# XIAO_RP2040_v1_22.net
KiCad netlist of a schematic drawn in EAGLE
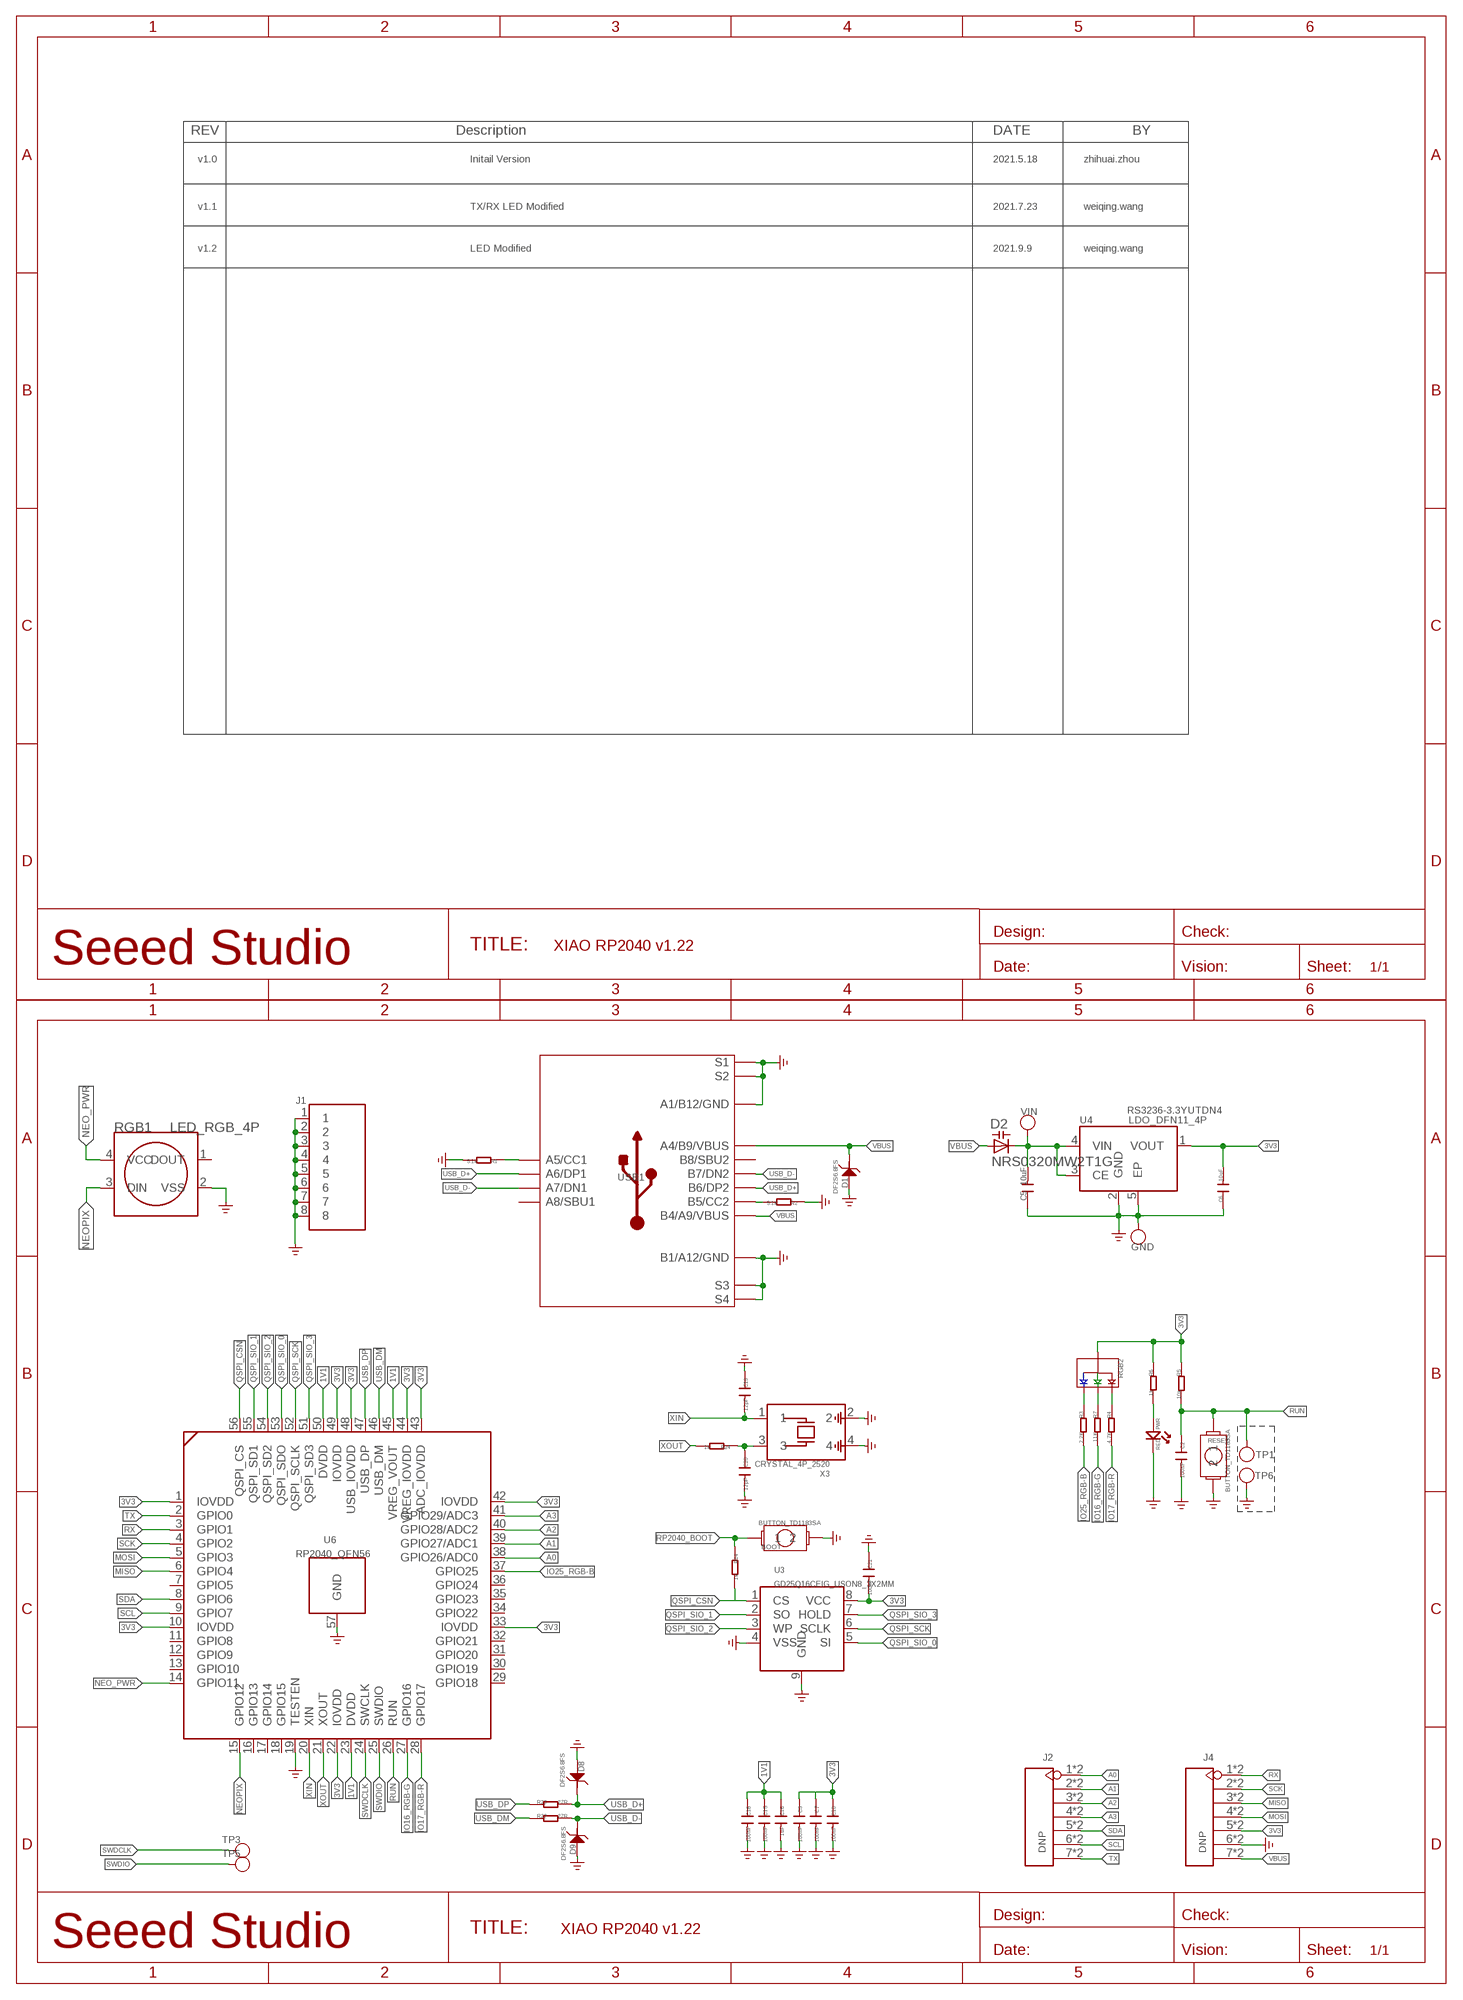
[diagram p0: schematic, sheet 1]

(export (version "E")
  (design (tool "Eeschema 10.0.6"))
  (components
    (comp (ref "BOOT")
      (value "BUTTON_TD1183SA")
      (footprint "eagle-import:BUTTON_TD1183SA")
      (libsource (lib "eagle-import") (part "BUTTON_TD1183SA"))
    )
    (comp (ref "C2")
      (value "100nF")
      (footprint "eagle-import:0201_NORMAL_NOSILK")
      (libsource (lib "eagle-import") (part "CAP{backslash}0201NNS"))
    )
    (comp (ref "C3")
      (value "100nF")
      (footprint "eagle-import:0201_NORMAL_NOSILK")
      (libsource (lib "eagle-import") (part "CAP{backslash}0201NNS"))
    )
    (comp (ref "C5")
      (value "10uF")
      (footprint "eagle-import:C0402")
      (libsource (lib "eagle-import") (part "C-0402"))
    )
    (comp (ref "C6")
      (value "10uF")
      (footprint "eagle-import:C0402")
      (libsource (lib "eagle-import") (part "C-0402"))
    )
    (comp (ref "C7")
      (value "100nF")
      (footprint "eagle-import:0201_NORMAL_NOSILK")
      (libsource (lib "eagle-import") (part "CAP{backslash}0201NNS"))
    )
    (comp (ref "C10")
      (value "100nF")
      (footprint "eagle-import:0201_NORMAL_NOSILK")
      (libsource (lib "eagle-import") (part "CAP{backslash}0201NNS"))
    )
    (comp (ref "C15")
      (value "100nF")
      (footprint "eagle-import:0201_NORMAL_NOSILK")
      (libsource (lib "eagle-import") (part "CAP{backslash}0201NNS"))
    )
    (comp (ref "C16")
      (value "1uF")
      (footprint "eagle-import:0201_NORMAL_NOSILK")
      (libsource (lib "eagle-import") (part "CAP{backslash}0201NNS"))
    )
    (comp (ref "C18")
      (value "100nF")
      (footprint "eagle-import:0201_NORMAL_NOSILK")
      (libsource (lib "eagle-import") (part "CAP{backslash}0201NNS"))
    )
    (comp (ref "C19")
      (value "12pF")
      (footprint "eagle-import:0201_NORMAL_NOSILK")
      (libsource (lib "eagle-import") (part "CAP{backslash}0201NNS"))
    )
    (comp (ref "C20")
      (value "12pF")
      (footprint "eagle-import:0201_NORMAL_NOSILK")
      (libsource (lib "eagle-import") (part "CAP{backslash}0201NNS"))
    )
    (comp (ref "C21")
      (value "100nF")
      (footprint "eagle-import:0201_NORMAL_NOSILK")
      (libsource (lib "eagle-import") (part "CAP{backslash}0201NNS"))
    )
    (comp (ref "D1")
      (value "DF2S6.8FS")
      (footprint "eagle-import:SOD-923")
      (libsource (lib "eagle-import") (part "D-ESD-2P'DF2S6.8FS'"))
    )
    (comp (ref "D2")
      (value "NRS0320MW2T1G")
      (footprint "eagle-import:SOD523")
      (libsource (lib "eagle-import") (part "DIODE_CAPACITANCE-SOD523"))
    )
    (comp (ref "D8")
      (value "DF2S6.8FS")
      (footprint "eagle-import:SOD-923")
      (libsource (lib "eagle-import") (part "D-ESD-2P'DF2S6.8FS'"))
    )
    (comp (ref "D9")
      (value "DF2S6.8FS")
      (footprint "eagle-import:SOD-923")
      (libsource (lib "eagle-import") (part "D-ESD-2P'DF2S6.8FS'"))
    )
    (comp (ref "GND")
      (value "TEST-POINT'4080'")
      (footprint "eagle-import:TP-80X40MIL")
      (libsource (lib "eagle-import") (part "TEST-POINT'4080'"))
    )
    (comp (ref "J1")
      (value "SHIELDING-COVER-XIAO_RP2040_PRD")
      (footprint "eagle-import:SHIELDING-COVER_XIAO_RP2040_PRD")
      (libsource (lib "eagle-import") (part "SHIELDING-COVER-XIAO_RP2040_PRD"))
    )
    (comp (ref "J2")
      (value "DNP")
      (footprint "eagle-import:H7-HALF-HOLE-2.54")
      (libsource (lib "eagle-import") (part "HEADER-7P-HALF-HOLE-2.54"))
    )
    (comp (ref "J4")
      (value "DNP")
      (footprint "eagle-import:H7-HALF-HOLE-2.54")
      (libsource (lib "eagle-import") (part "HEADER-7P-HALF-HOLE-2.54"))
    )
    (comp (ref "PWR")
      (value "RED")
      (footprint "eagle-import:LED-0402")
      (libsource (lib "eagle-import") (part "LED-0402"))
    )
    (comp (ref "R1")
      (value "5.1k")
      (footprint "eagle-import:R0201")
      (libsource (lib "eagle-import") (part "R-0201"))
    )
    (comp (ref "R2")
      (value "5.1k")
      (footprint "eagle-import:R0201")
      (libsource (lib "eagle-import") (part "R-0201"))
    )
    (comp (ref "R3")
      (value "2.2K")
      (footprint "eagle-import:R0201")
      (libsource (lib "eagle-import") (part "R-0201"))
    )
    (comp (ref "R4")
      (value "4.7K")
      (footprint "eagle-import:R0201")
      (libsource (lib "eagle-import") (part "R-0201"))
    )
    (comp (ref "R5")
      (value "10k")
      (footprint "eagle-import:R0201")
      (libsource (lib "eagle-import") (part "R-0201"))
    )
    (comp (ref "R6")
      (value "1k")
      (footprint "eagle-import:R0201")
      (libsource (lib "eagle-import") (part "R-0201"))
    )
    (comp (ref "R7")
      (value "11K")
      (footprint "eagle-import:R0201")
      (libsource (lib "eagle-import") (part "R-0201"))
    )
    (comp (ref "R14")
      (value "1k")
      (footprint "eagle-import:R0201")
      (libsource (lib "eagle-import") (part "R-0201"))
    )
    (comp (ref "R22")
      (value "27R")
      (footprint "eagle-import:R0201")
      (libsource (lib "eagle-import") (part "R-0201"))
    )
    (comp (ref "R23")
      (value "27R")
      (footprint "eagle-import:R0201")
      (libsource (lib "eagle-import") (part "R-0201"))
    )
    (comp (ref "R24")
      (value "1k")
      (footprint "eagle-import:R0201")
      (libsource (lib "eagle-import") (part "R-0201"))
    )
    (comp (ref "RESET")
      (value "BUTTON_TD1183SA")
      (footprint "eagle-import:BUTTON_TD1183SA")
      (libsource (lib "eagle-import") (part "BUTTON_TD1183SA"))
    )
    (comp (ref "RGB1")
      (value "LED_RGB_4P")
      (footprint "eagle-import:LED_RGB_2427")
      (libsource (lib "eagle-import") (part "LED_RGB_4P"))
    )
    (comp (ref "RGB2")
      (value "LED_RGB_4P-1010")
      (footprint "eagle-import:1010-4P")
      (libsource (lib "eagle-import") (part "LED_RGB_4P-1010"))
    )
    (comp (ref "TP1")
      (value "TEST-POINT'4545'")
      (footprint "eagle-import:TP-D45MIL")
      (fields (field (name "PARTNO") "DNP"))
      (libsource (lib "eagle-import") (part "TEST-POINT'4545'"))
    )
    (comp (ref "TP3")
      (value "TEST-POINT'4545'")
      (footprint "eagle-import:TP-D45MIL")
      (fields (field (name "PARTNO") "DNP"))
      (libsource (lib "eagle-import") (part "TEST-POINT'4545'"))
    )
    (comp (ref "TP5")
      (value "TEST-POINT'4545'")
      (footprint "eagle-import:TP-D45MIL")
      (fields (field (name "PARTNO") "DNP"))
      (libsource (lib "eagle-import") (part "TEST-POINT'4545'"))
    )
    (comp (ref "TP6")
      (value "TEST-POINT'4545'")
      (footprint "eagle-import:TP-D45MIL")
      (fields (field (name "PARTNO") "DNP"))
      (libsource (lib "eagle-import") (part "TEST-POINT'4545'"))
    )
    (comp (ref "U3")
      (value "GD25Q16CEIG_USON8_3X2MM")
      (footprint "eagle-import:GD25Q16CEIG_USON8_3X2MM")
      (libsource (lib "eagle-import") (part "GD25Q16CEIG_USON8_3X2MM"))
    )
    (comp (ref "U4")
      (value "LDO_DFN11_4P")
      (footprint "eagle-import:LDO_DFN1_1_4P")
      (libsource (lib "eagle-import") (part "LDO_DFN11_4P"))
    )
    (comp (ref "U6")
      (value "RP2040_QFN56")
      (footprint "eagle-import:RP2040_QFN56")
      (libsource (lib "eagle-import") (part "RP2040_QFN56"))
    )
    (comp (ref "USB1")
      (value "USB2.0-TYPE-C")
      (footprint "eagle-import:USB2.0-TYPE-C")
      (libsource (lib "eagle-import") (part "USB2.0-TYPE-C"))
    )
    (comp (ref "VIN")
      (value "TEST-POINT'4080'")
      (footprint "eagle-import:TP-80X40MIL")
      (libsource (lib "eagle-import") (part "TEST-POINT'4080'"))
    )
    (comp (ref "X3")
      (value "CRYSTAL_4P_2520")
      (footprint "eagle-import:CRYSTAL_4P_2520")
      (libsource (lib "eagle-import") (part "CRYSTAL_4P_2520"))
    )
  )
  (nets
    (net (code "1") (name "1V1") (class "Default")
      (node (ref "C15") (pin "1") (pinfunction "1_1") (pintype "passive"))
      (node (ref "C16") (pin "1") (pinfunction "1_1") (pintype "passive"))
      (node (ref "C18") (pin "1") (pinfunction "1_1") (pintype "passive"))
      (node (ref "U6") (pin "23") (pinfunction "DVDD_23") (pintype "bidirectional"))
      (node (ref "U6") (pin "45") (pinfunction "VREG_VOUT_45") (pintype "bidirectional"))
      (node (ref "U6") (pin "50") (pinfunction "DVDD_50") (pintype "bidirectional"))
    )
    (net (code "2") (name "3V3") (class "Default")
      (node (ref "C10") (pin "1") (pinfunction "1_1") (pintype "passive"))
      (node (ref "C21") (pin "2") (pinfunction "2_2") (pintype "passive"))
      (node (ref "C3") (pin "1") (pinfunction "1_1") (pintype "passive"))
      (node (ref "C6") (pin "2") (pinfunction "2_2") (pintype "passive"))
      (node (ref "C7") (pin "1") (pinfunction "1_1") (pintype "passive"))
      (node (ref "J4") (pin "17") (pinfunction "5_17") (pintype "bidirectional"))
      (node (ref "J4") (pin "5") (pinfunction "5_5") (pintype "bidirectional"))
      (node (ref "R5") (pin "1") (pinfunction "1_1") (pintype "passive"))
      (node (ref "R6") (pin "1") (pinfunction "1_1") (pintype "passive"))
      (node (ref "RGB2") (pin "+") (pinfunction "+_+") (pintype "bidirectional"))
      (node (ref "U3") (pin "8") (pinfunction "VCC_8") (pintype "bidirectional"))
      (node (ref "U4") (pin "1") (pinfunction "VOUT_1") (pintype "bidirectional"))
      (node (ref "U6") (pin "1") (pinfunction "IOVDD_1") (pintype "bidirectional"))
      (node (ref "U6") (pin "10") (pinfunction "IOVDD_10") (pintype "bidirectional"))
      (node (ref "U6") (pin "22") (pinfunction "IOVDD_22") (pintype "bidirectional"))
      (node (ref "U6") (pin "33") (pinfunction "IOVDD_33") (pintype "bidirectional"))
      (node (ref "U6") (pin "42") (pinfunction "IOVDD_42") (pintype "bidirectional"))
      (node (ref "U6") (pin "43") (pinfunction "ADC_IOVDD_43") (pintype "bidirectional"))
      (node (ref "U6") (pin "44") (pinfunction "VREG_IOVDD_44") (pintype "bidirectional"))
      (node (ref "U6") (pin "48") (pinfunction "USB_IOVDD_48") (pintype "bidirectional"))
      (node (ref "U6") (pin "49") (pinfunction "IOVDD_49") (pintype "bidirectional"))
    )
    (net (code "3") (name "A0") (class "Default")
      (node (ref "J2") (pin "1") (pinfunction "1_1") (pintype "bidirectional"))
      (node (ref "J2") (pin "13") (pinfunction "1_13") (pintype "bidirectional"))
      (node (ref "U6") (pin "38") (pinfunction "GPIO26/ADC0_38") (pintype "bidirectional"))
    )
    (net (code "4") (name "A1") (class "Default")
      (node (ref "J2") (pin "14") (pinfunction "2_14") (pintype "bidirectional"))
      (node (ref "J2") (pin "2") (pinfunction "2_2") (pintype "bidirectional"))
      (node (ref "U6") (pin "39") (pinfunction "GPIO27/ADC1_39") (pintype "bidirectional"))
    )
    (net (code "5") (name "A2") (class "Default")
      (node (ref "J2") (pin "15") (pinfunction "3_15") (pintype "bidirectional"))
      (node (ref "J2") (pin "3") (pinfunction "3_3") (pintype "bidirectional"))
      (node (ref "U6") (pin "40") (pinfunction "GPIO28/ADC2_40") (pintype "bidirectional"))
    )
    (net (code "6") (name "A3") (class "Default")
      (node (ref "J2") (pin "16") (pinfunction "4_16") (pintype "bidirectional"))
      (node (ref "J2") (pin "4") (pinfunction "4_4") (pintype "bidirectional"))
      (node (ref "U6") (pin "41") (pinfunction "GPIO29/ADC3_41") (pintype "bidirectional"))
    )
    (net (code "7") (name "GND_POWER") (class "Default")
      (node (ref "BOOT") (pin "2") (pinfunction "2_2") (pintype "bidirectional"))
      (node (ref "C10") (pin "2") (pinfunction "2_2") (pintype "passive"))
      (node (ref "C15") (pin "2") (pinfunction "2_2") (pintype "passive"))
      (node (ref "C16") (pin "2") (pinfunction "2_2") (pintype "passive"))
      (node (ref "C18") (pin "2") (pinfunction "2_2") (pintype "passive"))
      (node (ref "C19") (pin "1") (pinfunction "1_1") (pintype "passive"))
      (node (ref "C2") (pin "2") (pinfunction "2_2") (pintype "passive"))
      (node (ref "C20") (pin "2") (pinfunction "2_2") (pintype "passive"))
      (node (ref "C21") (pin "1") (pinfunction "1_1") (pintype "passive"))
      (node (ref "C3") (pin "2") (pinfunction "2_2") (pintype "passive"))
      (node (ref "C5") (pin "1") (pinfunction "1_1") (pintype "passive"))
      (node (ref "C6") (pin "1") (pinfunction "1_1") (pintype "passive"))
      (node (ref "C7") (pin "2") (pinfunction "2_2") (pintype "passive"))
      (node (ref "D1") (pin "2") (pinfunction "1_2") (pintype "bidirectional"))
      (node (ref "D8") (pin "2") (pinfunction "1_2") (pintype "bidirectional"))
      (node (ref "D9") (pin "2") (pinfunction "1_2") (pintype "bidirectional"))
      (node (ref "GND") (pin "1") (pinfunction "T_1") (pintype "bidirectional"))
      (node (ref "J1") (pin "1") (pinfunction "1_1") (pintype "bidirectional"))
      (node (ref "J1") (pin "2") (pinfunction "2_2") (pintype "bidirectional"))
      (node (ref "J1") (pin "3") (pinfunction "3_3") (pintype "bidirectional"))
      (node (ref "J1") (pin "4") (pinfunction "4_4") (pintype "bidirectional"))
      (node (ref "J1") (pin "5") (pinfunction "5_5") (pintype "bidirectional"))
      (node (ref "J1") (pin "6") (pinfunction "6_6") (pintype "bidirectional"))
      (node (ref "J1") (pin "7") (pinfunction "7_7") (pintype "bidirectional"))
      (node (ref "J1") (pin "8") (pinfunction "8_8") (pintype "bidirectional"))
      (node (ref "J4") (pin "18") (pinfunction "6_18") (pintype "bidirectional"))
      (node (ref "J4") (pin "6") (pinfunction "6_6") (pintype "bidirectional"))
      (node (ref "PWR") (pin "-") (pinfunction "-_-") (pintype "passive"))
      (node (ref "R1") (pin "2") (pinfunction "2_2") (pintype "passive"))
      (node (ref "R2") (pin "1") (pinfunction "1_1") (pintype "passive"))
      (node (ref "RESET") (pin "2") (pinfunction "2_2") (pintype "bidirectional"))
      (node (ref "RGB1") (pin "2") (pinfunction "VSS_2") (pintype "bidirectional"))
      (node (ref "TP6") (pin "T") (pinfunction "T_T") (pintype "bidirectional"))
      (node (ref "U3") (pin "4") (pinfunction "VSS_4") (pintype "bidirectional"))
      (node (ref "U3") (pin "9") (pinfunction "GND_9") (pintype "bidirectional"))
      (node (ref "U4") (pin "2") (pinfunction "GND_2") (pintype "bidirectional"))
      (node (ref "U4") (pin "5") (pinfunction "EP_5") (pintype "bidirectional"))
      (node (ref "U6") (pin "19") (pinfunction "TESTEN_19") (pintype "bidirectional"))
      (node (ref "U6") (pin "57") (pinfunction "GND_57") (pintype "bidirectional"))
      (node (ref "USB1") (pin "A1_B12") (pinfunction "A1/B12/GND_A1_B12") (pintype "bidirectional"))
      (node (ref "USB1") (pin "B1_A12") (pinfunction "B1/A12/GND_B1_A12") (pintype "bidirectional"))
      (node (ref "USB1") (pin "S1") (pinfunction "S1_S1") (pintype "bidirectional"))
      (node (ref "USB1") (pin "S2") (pinfunction "S2_S2") (pintype "bidirectional"))
      (node (ref "USB1") (pin "S3") (pinfunction "S3_S3") (pintype "bidirectional"))
      (node (ref "USB1") (pin "S4") (pinfunction "S4_S4") (pintype "bidirectional"))
      (node (ref "USB1") (pin "S5") (pinfunction "S1_S5") (pintype "bidirectional"))
      (node (ref "USB1") (pin "S6") (pinfunction "S2_S6") (pintype "bidirectional"))
      (node (ref "X3") (pin "2") (pinfunction "2_2") (pintype "bidirectional"))
      (node (ref "X3") (pin "4") (pinfunction "4_4") (pintype "bidirectional"))
    )
    (net (code "8") (name "IO16_RGB-G") (class "Default")
      (node (ref "R7") (pin "2") (pinfunction "2_2") (pintype "passive"))
      (node (ref "U6") (pin "27") (pinfunction "GPIO16_27") (pintype "bidirectional"))
    )
    (net (code "9") (name "IO17_RGB-R") (class "Default")
      (node (ref "R4") (pin "2") (pinfunction "2_2") (pintype "passive"))
      (node (ref "U6") (pin "28") (pinfunction "GPIO17_28") (pintype "bidirectional"))
    )
    (net (code "10") (name "IO25_RGB-B") (class "Default")
      (node (ref "R3") (pin "2") (pinfunction "2_2") (pintype "passive"))
      (node (ref "U6") (pin "37") (pinfunction "GPIO25_37") (pintype "bidirectional"))
    )
    (net (code "11") (name "MISO") (class "Default")
      (node (ref "J4") (pin "15") (pinfunction "3_15") (pintype "bidirectional"))
      (node (ref "J4") (pin "3") (pinfunction "3_3") (pintype "bidirectional"))
      (node (ref "U6") (pin "6") (pinfunction "GPIO4_6") (pintype "bidirectional"))
    )
    (net (code "12") (name "MOSI") (class "Default")
      (node (ref "J4") (pin "16") (pinfunction "4_16") (pintype "bidirectional"))
      (node (ref "J4") (pin "4") (pinfunction "4_4") (pintype "bidirectional"))
      (node (ref "U6") (pin "5") (pinfunction "GPIO3_5") (pintype "bidirectional"))
    )
    (net (code "13") (name "NEOPIX") (class "Default")
      (node (ref "RGB1") (pin "3") (pinfunction "DIN_3") (pintype "bidirectional"))
      (node (ref "U6") (pin "15") (pinfunction "GPIO12_15") (pintype "bidirectional"))
    )
    (net (code "14") (name "NEO_PWR") (class "Default")
      (node (ref "RGB1") (pin "4") (pinfunction "VCC_4") (pintype "bidirectional"))
      (node (ref "U6") (pin "14") (pinfunction "GPIO11_14") (pintype "bidirectional"))
    )
    (net (code "15") (name "Net-(C20-Pad1)") (class "Default")
      (node (ref "C20") (pin "1") (pinfunction "1_1") (pintype "passive"))
      (node (ref "R24") (pin "1") (pinfunction "1_1") (pintype "passive"))
      (node (ref "X3") (pin "3") (pinfunction "3_3") (pintype "bidirectional"))
    )
    (net (code "16") (name "Net-(PWR-Pad+)") (class "Default")
      (node (ref "PWR") (pin "+") (pinfunction "+_+") (pintype "passive"))
      (node (ref "R6") (pin "2") (pinfunction "2_2") (pintype "passive"))
    )
    (net (code "17") (name "Net-(R3-Pad1)") (class "Default")
      (node (ref "R3") (pin "1") (pinfunction "1_1") (pintype "passive"))
      (node (ref "RGB2") (pin "B-") (pinfunction "B-_B-") (pintype "bidirectional"))
    )
    (net (code "18") (name "Net-(R4-Pad1)") (class "Default")
      (node (ref "R4") (pin "1") (pinfunction "1_1") (pintype "passive"))
      (node (ref "RGB2") (pin "R-") (pinfunction "R-_R-") (pintype "bidirectional"))
    )
    (net (code "19") (name "Net-(R7-Pad1)") (class "Default")
      (node (ref "R7") (pin "1") (pinfunction "1_1") (pintype "passive"))
      (node (ref "RGB2") (pin "G-") (pinfunction "G-_G-") (pintype "bidirectional"))
    )
    (net (code "20") (name "Net-(U4-CE)") (class "Default")
      (node (ref "C5") (pin "2") (pinfunction "2_2") (pintype "passive"))
      (node (ref "D2") (pin "C") (pinfunction "C_C") (pintype "passive"))
      (node (ref "U4") (pin "3") (pinfunction "CE_3") (pintype "bidirectional"))
      (node (ref "U4") (pin "4") (pinfunction "VIN_4") (pintype "bidirectional"))
      (node (ref "VIN") (pin "1") (pinfunction "T_1") (pintype "bidirectional"))
    )
    (net (code "21") (name "Net-(USB1-A5{slash}CC1)") (class "Default")
      (node (ref "R1") (pin "1") (pinfunction "1_1") (pintype "passive"))
      (node (ref "USB1") (pin "A5") (pinfunction "A5/CC1_A5") (pintype "bidirectional"))
    )
    (net (code "22") (name "Net-(USB1-B5{slash}CC2)") (class "Default")
      (node (ref "R2") (pin "2") (pinfunction "2_2") (pintype "passive"))
      (node (ref "USB1") (pin "B5") (pinfunction "B5/CC2_B5") (pintype "bidirectional"))
    )
    (net (code "23") (name "QSPI_CSN") (class "Default")
      (node (ref "R14") (pin "2") (pinfunction "2_2") (pintype "passive"))
      (node (ref "U3") (pin "1") (pinfunction "CS_1") (pintype "bidirectional"))
      (node (ref "U6") (pin "56") (pinfunction "QSPI_CS_56") (pintype "bidirectional"))
    )
    (net (code "24") (name "QSPI_SCK") (class "Default")
      (node (ref "U3") (pin "6") (pinfunction "SCLK_6") (pintype "bidirectional"))
      (node (ref "U6") (pin "52") (pinfunction "QSPI_SCLK_52") (pintype "bidirectional"))
    )
    (net (code "25") (name "QSPI_SIO_0") (class "Default")
      (node (ref "U3") (pin "5") (pinfunction "SI_5") (pintype "bidirectional"))
      (node (ref "U6") (pin "53") (pinfunction "QSPI_SDO_53") (pintype "bidirectional"))
    )
    (net (code "26") (name "QSPI_SIO_1") (class "Default")
      (node (ref "U3") (pin "2") (pinfunction "SO_2") (pintype "bidirectional"))
      (node (ref "U6") (pin "55") (pinfunction "QSPI_SD1_55") (pintype "bidirectional"))
    )
    (net (code "27") (name "QSPI_SIO_2") (class "Default")
      (node (ref "U3") (pin "3") (pinfunction "WP_3") (pintype "bidirectional"))
      (node (ref "U6") (pin "54") (pinfunction "QSPI_SD2_54") (pintype "bidirectional"))
    )
    (net (code "28") (name "QSPI_SIO_3") (class "Default")
      (node (ref "U3") (pin "7") (pinfunction "HOLD_7") (pintype "bidirectional"))
      (node (ref "U6") (pin "51") (pinfunction "QSPI_SD3_51") (pintype "bidirectional"))
    )
    (net (code "29") (name "RP2040_BOOT") (class "Default")
      (node (ref "BOOT") (pin "1") (pinfunction "1_1") (pintype "bidirectional"))
      (node (ref "R14") (pin "1") (pinfunction "1_1") (pintype "passive"))
    )
    (net (code "30") (name "RUN") (class "Default")
      (node (ref "C2") (pin "1") (pinfunction "1_1") (pintype "passive"))
      (node (ref "R5") (pin "2") (pinfunction "2_2") (pintype "passive"))
      (node (ref "RESET") (pin "1") (pinfunction "1_1") (pintype "bidirectional"))
      (node (ref "TP1") (pin "T") (pinfunction "T_T") (pintype "bidirectional"))
      (node (ref "U6") (pin "26") (pinfunction "RUN_26") (pintype "bidirectional"))
    )
    (net (code "31") (name "RX") (class "Default")
      (node (ref "J4") (pin "1") (pinfunction "1_1") (pintype "bidirectional"))
      (node (ref "J4") (pin "13") (pinfunction "1_13") (pintype "bidirectional"))
      (node (ref "U6") (pin "3") (pinfunction "GPIO1_3") (pintype "bidirectional"))
    )
    (net (code "32") (name "SCK") (class "Default")
      (node (ref "J4") (pin "14") (pinfunction "2_14") (pintype "bidirectional"))
      (node (ref "J4") (pin "2") (pinfunction "2_2") (pintype "bidirectional"))
      (node (ref "U6") (pin "4") (pinfunction "GPIO2_4") (pintype "bidirectional"))
    )
    (net (code "33") (name "SCL") (class "Default")
      (node (ref "J2") (pin "18") (pinfunction "6_18") (pintype "bidirectional"))
      (node (ref "J2") (pin "6") (pinfunction "6_6") (pintype "bidirectional"))
      (node (ref "U6") (pin "9") (pinfunction "GPIO7_9") (pintype "bidirectional"))
    )
    (net (code "34") (name "SDA") (class "Default")
      (node (ref "J2") (pin "17") (pinfunction "5_17") (pintype "bidirectional"))
      (node (ref "J2") (pin "5") (pinfunction "5_5") (pintype "bidirectional"))
      (node (ref "U6") (pin "8") (pinfunction "GPIO6_8") (pintype "bidirectional"))
    )
    (net (code "35") (name "SWDCLK") (class "Default")
      (node (ref "TP3") (pin "T") (pinfunction "T_T") (pintype "bidirectional"))
      (node (ref "U6") (pin "24") (pinfunction "SWCLK_24") (pintype "bidirectional"))
    )
    (net (code "36") (name "SWDIO") (class "Default")
      (node (ref "TP5") (pin "T") (pinfunction "T_T") (pintype "bidirectional"))
      (node (ref "U6") (pin "25") (pinfunction "SWDIO_25") (pintype "bidirectional"))
    )
    (net (code "37") (name "TX") (class "Default")
      (node (ref "J2") (pin "19") (pinfunction "7_19") (pintype "bidirectional"))
      (node (ref "J2") (pin "7") (pinfunction "7_7") (pintype "bidirectional"))
      (node (ref "U6") (pin "2") (pinfunction "GPIO0_2") (pintype "bidirectional"))
    )
    (net (code "38") (name "USB_D+") (class "Default")
      (node (ref "D8") (pin "1") (pinfunction "2_1") (pintype "bidirectional"))
      (node (ref "R23") (pin "2") (pinfunction "2_2") (pintype "passive"))
      (node (ref "USB1") (pin "A6") (pinfunction "A6/DP1_A6") (pintype "bidirectional"))
      (node (ref "USB1") (pin "B6") (pinfunction "B6/DP2_B6") (pintype "bidirectional"))
    )
    (net (code "39") (name "USB_D-") (class "Default")
      (node (ref "D9") (pin "1") (pinfunction "2_1") (pintype "bidirectional"))
      (node (ref "R22") (pin "2") (pinfunction "2_2") (pintype "passive"))
      (node (ref "USB1") (pin "A7") (pinfunction "A7/DN1_A7") (pintype "bidirectional"))
      (node (ref "USB1") (pin "B7") (pinfunction "B7/DN2_B7") (pintype "bidirectional"))
    )
    (net (code "40") (name "USB_DM") (class "Default")
      (node (ref "R22") (pin "1") (pinfunction "1_1") (pintype "passive"))
      (node (ref "U6") (pin "46") (pinfunction "USB_DM_46") (pintype "bidirectional"))
    )
    (net (code "41") (name "USB_DP") (class "Default")
      (node (ref "R23") (pin "1") (pinfunction "1_1") (pintype "passive"))
      (node (ref "U6") (pin "47") (pinfunction "USB_DP_47") (pintype "bidirectional"))
    )
    (net (code "42") (name "VBUS") (class "Default")
      (node (ref "D1") (pin "1") (pinfunction "2_1") (pintype "bidirectional"))
      (node (ref "D2") (pin "A") (pinfunction "A_A") (pintype "passive"))
      (node (ref "J4") (pin "19") (pinfunction "7_19") (pintype "bidirectional"))
      (node (ref "J4") (pin "7") (pinfunction "7_7") (pintype "bidirectional"))
      (node (ref "USB1") (pin "A4_B9") (pinfunction "A4/B9/VBUS_A4_B9") (pintype "bidirectional"))
      (node (ref "USB1") (pin "B4_A9") (pinfunction "B4/A9/VBUS_B4_A9") (pintype "bidirectional"))
    )
    (net (code "43") (name "XIN") (class "Default")
      (node (ref "C19") (pin "2") (pinfunction "2_2") (pintype "passive"))
      (node (ref "U6") (pin "20") (pinfunction "XIN_20") (pintype "bidirectional"))
      (node (ref "X3") (pin "1") (pinfunction "1_1") (pintype "bidirectional"))
    )
    (net (code "44") (name "XOUT") (class "Default")
      (node (ref "R24") (pin "2") (pinfunction "2_2") (pintype "passive"))
      (node (ref "U6") (pin "21") (pinfunction "XOUT_21") (pintype "bidirectional"))
    )
    (net (code "45") (name "unconnected-(RGB1-DOUT-Pad1)") (class "Default")
      (node (ref "RGB1") (pin "1") (pinfunction "DOUT_1") (pintype "bidirectional"))
    )
    (net (code "46") (name "unconnected-(U6-GPIO5-Pad7)") (class "Default")
      (node (ref "U6") (pin "7") (pinfunction "GPIO5_7") (pintype "bidirectional"))
    )
    (net (code "47") (name "unconnected-(U6-GPIO8-Pad11)") (class "Default")
      (node (ref "U6") (pin "11") (pinfunction "GPIO8_11") (pintype "bidirectional"))
    )
    (net (code "48") (name "unconnected-(U6-GPIO9-Pad12)") (class "Default")
      (node (ref "U6") (pin "12") (pinfunction "GPIO9_12") (pintype "bidirectional"))
    )
    (net (code "49") (name "unconnected-(U6-GPIO10-Pad13)") (class "Default")
      (node (ref "U6") (pin "13") (pinfunction "GPIO10_13") (pintype "bidirectional"))
    )
    (net (code "50") (name "unconnected-(U6-GPIO13-Pad16)") (class "Default")
      (node (ref "U6") (pin "16") (pinfunction "GPIO13_16") (pintype "bidirectional"))
    )
    (net (code "51") (name "unconnected-(U6-GPIO14-Pad17)") (class "Default")
      (node (ref "U6") (pin "17") (pinfunction "GPIO14_17") (pintype "bidirectional"))
    )
    (net (code "52") (name "unconnected-(U6-GPIO15-Pad18)") (class "Default")
      (node (ref "U6") (pin "18") (pinfunction "GPIO15_18") (pintype "bidirectional"))
    )
    (net (code "53") (name "unconnected-(U6-GPIO18-Pad29)") (class "Default")
      (node (ref "U6") (pin "29") (pinfunction "GPIO18_29") (pintype "bidirectional"))
    )
    (net (code "54") (name "unconnected-(U6-GPIO19-Pad30)") (class "Default")
      (node (ref "U6") (pin "30") (pinfunction "GPIO19_30") (pintype "bidirectional"))
    )
    (net (code "55") (name "unconnected-(U6-GPIO20-Pad31)") (class "Default")
      (node (ref "U6") (pin "31") (pinfunction "GPIO20_31") (pintype "bidirectional"))
    )
    (net (code "56") (name "unconnected-(U6-GPIO21-Pad32)") (class "Default")
      (node (ref "U6") (pin "32") (pinfunction "GPIO21_32") (pintype "bidirectional"))
    )
    (net (code "57") (name "unconnected-(U6-GPIO22-Pad34)") (class "Default")
      (node (ref "U6") (pin "34") (pinfunction "GPIO22_34") (pintype "bidirectional"))
    )
    (net (code "58") (name "unconnected-(U6-GPIO23-Pad35)") (class "Default")
      (node (ref "U6") (pin "35") (pinfunction "GPIO23_35") (pintype "bidirectional"))
    )
    (net (code "59") (name "unconnected-(U6-GPIO24-Pad36)") (class "Default")
      (node (ref "U6") (pin "36") (pinfunction "GPIO24_36") (pintype "bidirectional"))
    )
    (net (code "60") (name "unconnected-(USB1-A8{slash}SBU1-PadA8)") (class "Default")
      (node (ref "USB1") (pin "A8") (pinfunction "A8/SBU1_A8") (pintype "bidirectional"))
    )
    (net (code "61") (name "unconnected-(USB1-B8{slash}SBU2-PadB8)") (class "Default")
      (node (ref "USB1") (pin "B8") (pinfunction "B8/SBU2_B8") (pintype "bidirectional"))
    )
  )
)
